# Sh_Coccinelle.net
KiCad netlist of a schematic drawn in Altium Designer
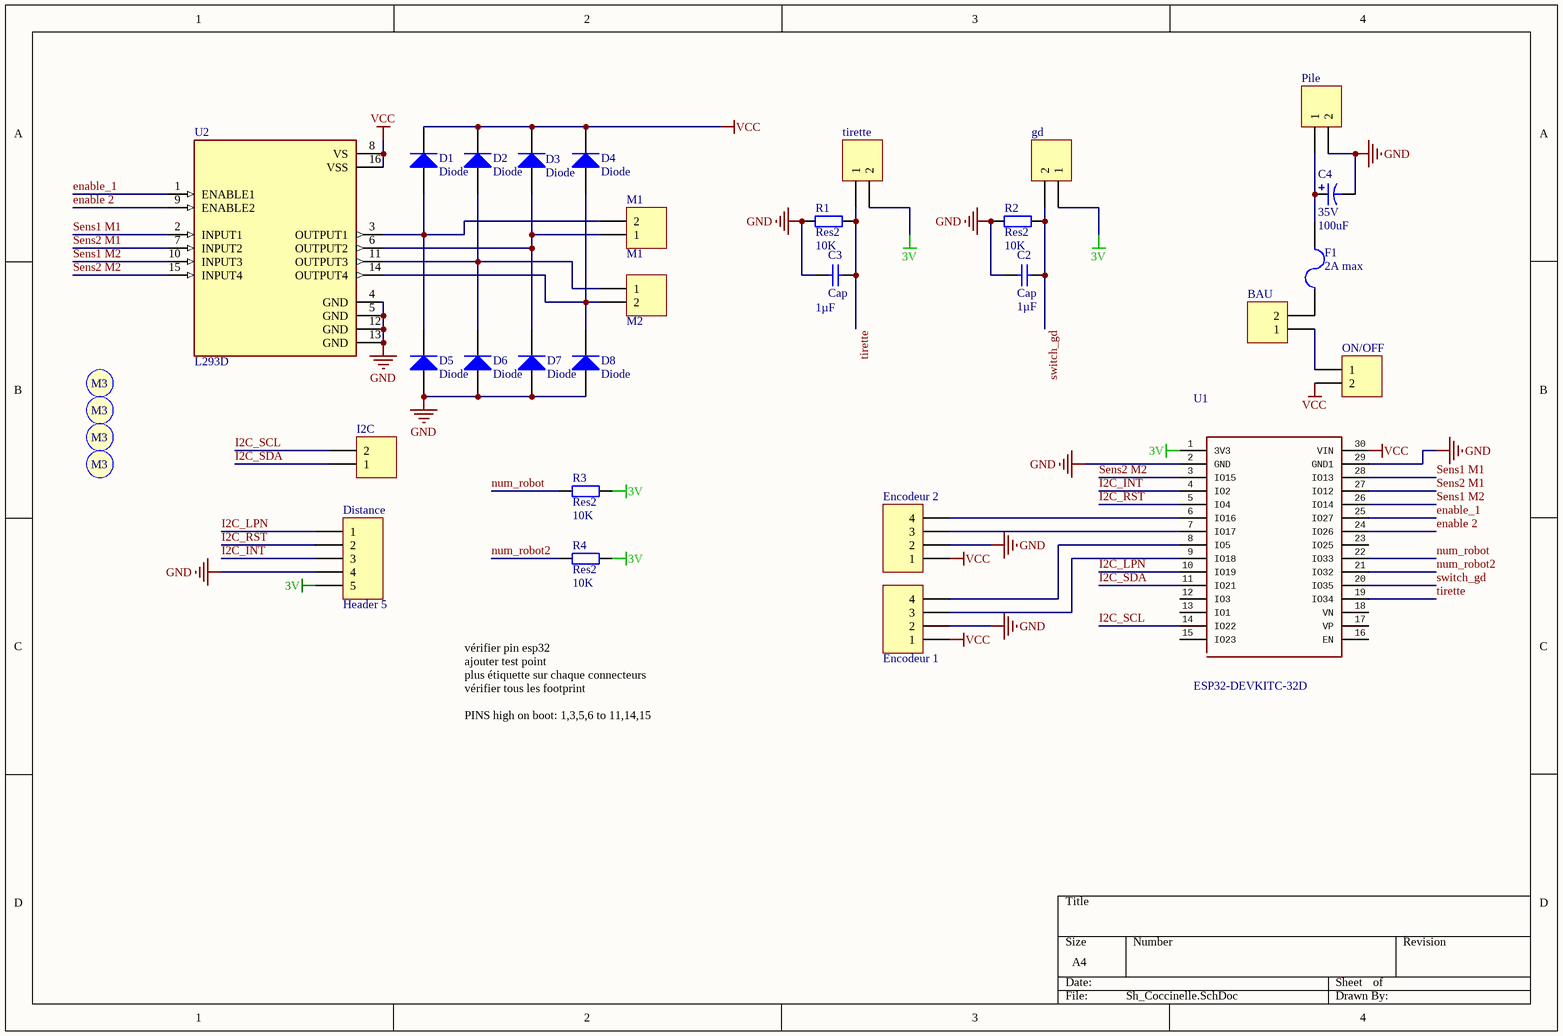
[diagram p0: Sh_Coccinelle.SchDoc]

(export (version "E")
  (design (tool "Eeschema 10.0.6"))
  (components
    (comp (ref "BAU")
      (value "~")
      (footprint "S2B-XH-A")
      (description "Header, 2-Pin, Right Angle")
      (fields (field (name "PUBLISHER") "Altium Limited"))
      (libsource (lib "Miscellaneous Connectors") (part "Header 2H"))
    )
    (comp (ref "C2")
      (value "Cap")
      (footprint "Capacitor 1206")
      (description "Capacitor")
      (fields (field (name "ALTIUM_VALUE") "1µF") (field (name "PUBLISHER") "Altium Limited"))
      (libsource (lib "Miscellaneous Devices") (part "Cap"))
    )
    (comp (ref "C3")
      (value "Cap")
      (footprint "Capacitor 1206")
      (description "Capacitor")
      (fields (field (name "ALTIUM_VALUE") "1µF") (field (name "PUBLISHER") "Altium Limited"))
      (libsource (lib "Miscellaneous Devices") (part "Cap"))
    )
    (comp (ref "C4")
      (value "35V")
      (footprint "Condensateur")
      (description "Polarized Capacitor (Radial)")
      (fields (field (name "ALTIUM_VALUE") "100uF") (field (name "PUBLISHER") "Altium Limited"))
      (libsource (lib "Miscellaneous Devices") (part "Cap Pol1"))
    )
    (comp (ref "D1")
      (value "Diode")
      (footprint "SMB")
      (description "Default Diode")
      (fields (field (name "PUBLISHER") "Altium Limited"))
      (libsource (lib "Miscellaneous Devices") (part "Diode"))
    )
    (comp (ref "D2")
      (value "Diode")
      (footprint "SMB")
      (description "Default Diode")
      (fields (field (name "PUBLISHER") "Altium Limited"))
      (libsource (lib "Miscellaneous Devices") (part "Diode"))
    )
    (comp (ref "D3")
      (value "Diode")
      (footprint "SMB")
      (description "Default Diode")
      (fields (field (name "PUBLISHER") "Altium Limited"))
      (libsource (lib "Miscellaneous Devices") (part "Diode"))
    )
    (comp (ref "D4")
      (value "Diode")
      (footprint "SMB")
      (description "Default Diode")
      (fields (field (name "PUBLISHER") "Altium Limited"))
      (libsource (lib "Miscellaneous Devices") (part "Diode"))
    )
    (comp (ref "D5")
      (value "Diode")
      (footprint "SMB")
      (description "Default Diode")
      (fields (field (name "PUBLISHER") "Altium Limited"))
      (libsource (lib "Miscellaneous Devices") (part "Diode"))
    )
    (comp (ref "D6")
      (value "Diode")
      (footprint "SMB")
      (description "Default Diode")
      (fields (field (name "PUBLISHER") "Altium Limited"))
      (libsource (lib "Miscellaneous Devices") (part "Diode"))
    )
    (comp (ref "D7")
      (value "Diode")
      (footprint "SMB")
      (description "Default Diode")
      (fields (field (name "PUBLISHER") "Altium Limited"))
      (libsource (lib "Miscellaneous Devices") (part "Diode"))
    )
    (comp (ref "D8")
      (value "Diode")
      (footprint "SMB")
      (description "Default Diode")
      (fields (field (name "PUBLISHER") "Altium Limited"))
      (libsource (lib "Miscellaneous Devices") (part "Diode"))
    )
    (comp (ref "Distance")
      (value "Header 5")
      (footprint "B5BXHAMLFSN")
      (description "Header, 5-Pin")
      (fields (field (name "PUBLISHER") "Altium Limited"))
      (libsource (lib "Miscellaneous Connectors") (part "Header 5"))
    )
    (comp (ref "Encodeur 1")
      (value "~")
      (footprint "B4BXHALFSN")
      (description "Header, 4-Pin, Right Angle")
      (fields (field (name "PUBLISHER") "Altium Limited"))
      (libsource (lib "Miscellaneous Connectors") (part "Header 4H"))
    )
    (comp (ref "Encodeur 2")
      (value "~")
      (footprint "B4BXHALFSN")
      (description "Header, 4-Pin, Right Angle")
      (fields (field (name "PUBLISHER") "Altium Limited"))
      (libsource (lib "Miscellaneous Connectors") (part "Header 4H"))
    )
    (comp (ref "F1")
      (value "2A max")
      (footprint "PIN-W2/E2.8")
      (description "Fuse")
      (fields (field (name "PUBLISHER") "Altium Limited"))
      (libsource (lib "Miscellaneous Devices") (part "Fuse 2"))
    )
    (comp (ref "gd")
      (value "~")
      (footprint "S2B-XH-A")
      (description "Header, 2-Pin, Right Angle")
      (fields (field (name "PUBLISHER") "Altium Limited"))
      (libsource (lib "") (part "Header 2H_1"))
    )
    (comp (ref "I2C")
      (value "~")
      (footprint "S2B-XH-A")
      (description "Header, 2-Pin, Right Angle")
      (fields (field (name "PUBLISHER") "Altium Limited"))
      (libsource (lib "") (part "Header 2H_2"))
    )
    (comp (ref "M1")
      (value "M1")
      (footprint "S2B-XH-A")
      (description "Header, 2-Pin, Right Angle")
      (fields (field (name "PUBLISHER") "Altium Limited"))
      (libsource (lib "") (part "Header 2H_2"))
    )
    (comp (ref "M2")
      (value "M2")
      (footprint "S2B-XH-A")
      (description "Header, 2-Pin, Right Angle")
      (fields (field (name "PUBLISHER") "Altium Limited"))
      (libsource (lib "") (part "Header 2H_1"))
    )
    (comp (ref "ON/OFF")
      (value "~")
      (footprint "S2B-XH-A")
      (description "Header, 2-Pin, Right Angle")
      (fields (field (name "PUBLISHER") "Altium Limited"))
      (libsource (lib "") (part "Header 2H_1"))
    )
    (comp (ref "Pile")
      (value "~")
      (footprint "S2B-XH-A")
      (description "Header, 2-Pin, Right Angle")
      (fields (field (name "PUBLISHER") "Altium Limited"))
      (libsource (lib "") (part "Header 2H_2"))
    )
    (comp (ref "R1")
      (value "Res2")
      (footprint "Resistor 1206")
      (description "Resistor")
      (fields (field (name "ALTIUM_VALUE") "10K") (field (name "PUBLISHER") "Altium Limited"))
      (libsource (lib "Miscellaneous Devices") (part "Res2"))
    )
    (comp (ref "R2")
      (value "Res2")
      (footprint "Resistor 1206")
      (description "Resistor")
      (fields (field (name "ALTIUM_VALUE") "10K") (field (name "PUBLISHER") "Altium Limited"))
      (libsource (lib "Miscellaneous Devices") (part "Res2"))
    )
    (comp (ref "R3")
      (value "Res2")
      (footprint "Resistor 1206")
      (description "Resistor")
      (fields (field (name "ALTIUM_VALUE") "10K") (field (name "PUBLISHER") "Altium Limited"))
      (libsource (lib "Miscellaneous Devices") (part "Res2"))
    )
    (comp (ref "R4")
      (value "Res2")
      (footprint "Resistor 1206")
      (description "Resistor")
      (fields (field (name "ALTIUM_VALUE") "10K") (field (name "PUBLISHER") "Altium Limited"))
      (libsource (lib "Miscellaneous Devices") (part "Res2"))
    )
    (comp (ref "S1")
      (value "Screw M3")
      (footprint "Screw M3")
      (libsource (lib "Robot_2020") (part "Screw M3"))
    )
    (comp (ref "S2")
      (value "Screw M3")
      (footprint "Screw M3")
      (libsource (lib "Robot_2020") (part "Screw M3"))
    )
    (comp (ref "S3")
      (value "Screw M3")
      (footprint "Screw M3")
      (libsource (lib "Robot_2020") (part "Screw M3"))
    )
    (comp (ref "S4")
      (value "Screw M3")
      (footprint "Screw M3")
      (libsource (lib "Robot_2020") (part "Screw M3"))
    )
    (comp (ref "tirette")
      (value "~")
      (footprint "S2B-XH-A")
      (description "Header, 2-Pin, Right Angle")
      (fields (field (name "PUBLISHER") "Altium Limited"))
      (libsource (lib "") (part "Header 2H_2"))
    )
    (comp (ref "U1")
      (value "ESP32-DEVKITC-32D")
      (footprint "MODULE_ESP32-DEVKITV1")
      (description "Eval Board For Esp-Wroom-32")
      (fields (field (name "MF") "Espressif Systems"))
      (libsource (lib "AltiumLibraryDDT") (part "ESP32-DEVKITC-32D"))
    )
    (comp (ref "U2")
      (value "L293D")
      (footprint "DIP880W50P254L2000H510Q16")
      (description "Bipolar Motor Driver - Parallel 16-PowerDIP")
      (fields (field (name "MF") "STMicroelectronics"))
      (libsource (lib "L293D") (part "L293D"))
    )
  )
  (nets
    (net (code "1") (name "/I2C_INT") (class "Default")
      (node (ref "Distance") (pin "3") (pinfunction "3_3") (pintype "passive"))
      (node (ref "U1") (pin "4") (pinfunction "IO2_4") (pintype "passive"))
    )
    (net (code "2") (name "/I2C_LPN") (class "Default")
      (node (ref "Distance") (pin "1") (pinfunction "1_1") (pintype "passive"))
      (node (ref "U1") (pin "10") (pinfunction "IO19_10") (pintype "passive"))
    )
    (net (code "3") (name "/I2C_RST") (class "Default")
      (node (ref "Distance") (pin "2") (pinfunction "2_2") (pintype "passive"))
      (node (ref "U1") (pin "5") (pinfunction "IO4_5") (pintype "passive"))
    )
    (net (code "4") (name "/I2C_SCL") (class "Default")
      (node (ref "I2C") (pin "2") (pinfunction "2_2") (pintype "passive"))
      (node (ref "U1") (pin "14") (pinfunction "IO22_14") (pintype "passive"))
    )
    (net (code "5") (name "/I2C_SDA") (class "Default")
      (node (ref "I2C") (pin "1") (pinfunction "1_1") (pintype "passive"))
      (node (ref "U1") (pin "11") (pinfunction "IO21_11") (pintype "passive"))
    )
    (net (code "6") (name "/Sens1 M1") (class "Default")
      (node (ref "U1") (pin "28") (pinfunction "IO13_28") (pintype "passive"))
      (node (ref "U2") (pin "2") (pinfunction "INPUT1_2") (pintype "input"))
    )
    (net (code "7") (name "/Sens1 M2") (class "Default")
      (node (ref "U1") (pin "26") (pinfunction "IO14_26") (pintype "passive"))
      (node (ref "U2") (pin "10") (pinfunction "INPUT3_10") (pintype "input"))
    )
    (net (code "8") (name "/Sens2 M1") (class "Default")
      (node (ref "U1") (pin "27") (pinfunction "IO12_27") (pintype "passive"))
      (node (ref "U2") (pin "7") (pinfunction "INPUT2_7") (pintype "input"))
    )
    (net (code "9") (name "/Sens2 M2") (class "Default")
      (node (ref "U1") (pin "3") (pinfunction "IO15_3") (pintype "passive"))
      (node (ref "U2") (pin "15") (pinfunction "INPUT4_15") (pintype "input"))
    )
    (net (code "10") (name "/enable 2") (class "Default")
      (node (ref "U1") (pin "24") (pinfunction "IO26_24") (pintype "passive"))
      (node (ref "U2") (pin "9") (pinfunction "ENABLE2_9") (pintype "input"))
    )
    (net (code "11") (name "/enable_1") (class "Default")
      (node (ref "U1") (pin "25") (pinfunction "IO27_25") (pintype "passive"))
      (node (ref "U2") (pin "1") (pinfunction "ENABLE1_1") (pintype "input"))
    )
    (net (code "12") (name "/num_robot") (class "Default")
      (node (ref "R3") (pin "1") (pinfunction "1_1") (pintype "passive"))
      (node (ref "U1") (pin "22") (pinfunction "IO33_22") (pintype "passive"))
    )
    (net (code "13") (name "/num_robot2") (class "Default")
      (node (ref "R4") (pin "1") (pinfunction "1_1") (pintype "passive"))
      (node (ref "U1") (pin "21") (pinfunction "IO32_21") (pintype "passive"))
    )
    (net (code "14") (name "/switch_gd") (class "Default")
      (node (ref "C2") (pin "2") (pinfunction "2_2") (pintype "passive"))
      (node (ref "R2") (pin "2") (pinfunction "2_2") (pintype "passive"))
      (node (ref "U1") (pin "20") (pinfunction "IO35_20") (pintype "passive"))
      (node (ref "gd") (pin "2") (pinfunction "2_2") (pintype "passive"))
    )
    (net (code "15") (name "/tirette") (class "Default")
      (node (ref "C3") (pin "2") (pinfunction "2_2") (pintype "passive"))
      (node (ref "R1") (pin "2") (pinfunction "2_2") (pintype "passive"))
      (node (ref "U1") (pin "19") (pinfunction "IO34_19") (pintype "passive"))
      (node (ref "tirette") (pin "1") (pinfunction "1_1") (pintype "passive"))
    )
    (net (code "16") (name "3V") (class "Default")
      (node (ref "Distance") (pin "5") (pinfunction "5_5") (pintype "passive"))
      (node (ref "R3") (pin "2") (pinfunction "2_2") (pintype "passive"))
      (node (ref "R4") (pin "2") (pinfunction "2_2") (pintype "passive"))
      (node (ref "U1") (pin "1") (pinfunction "3V3_1") (pintype "passive"))
      (node (ref "gd") (pin "1") (pinfunction "1_1") (pintype "passive"))
      (node (ref "tirette") (pin "2") (pinfunction "2_2") (pintype "passive"))
    )
    (net (code "17") (name "GND") (class "Default")
      (node (ref "C2") (pin "1") (pinfunction "1_1") (pintype "passive"))
      (node (ref "C3") (pin "1") (pinfunction "1_1") (pintype "passive"))
      (node (ref "C4") (pin "2") (pinfunction "2_2") (pintype "passive"))
      (node (ref "D5") (pin "1") (pinfunction "A_1") (pintype "passive"))
      (node (ref "D6") (pin "1") (pinfunction "A_1") (pintype "passive"))
      (node (ref "D7") (pin "1") (pinfunction "A_1") (pintype "passive"))
      (node (ref "D8") (pin "1") (pinfunction "A_1") (pintype "passive"))
      (node (ref "Distance") (pin "4") (pinfunction "4_4") (pintype "passive"))
      (node (ref "Encodeur 1") (pin "2") (pinfunction "2_2") (pintype "passive"))
      (node (ref "Encodeur 2") (pin "2") (pinfunction "2_2") (pintype "passive"))
      (node (ref "Pile") (pin "2") (pinfunction "2_2") (pintype "passive"))
      (node (ref "R1") (pin "1") (pinfunction "1_1") (pintype "passive"))
      (node (ref "R2") (pin "1") (pinfunction "1_1") (pintype "passive"))
      (node (ref "U1") (pin "2") (pinfunction "GND_2") (pintype "passive"))
      (node (ref "U1") (pin "29") (pinfunction "GND1_29") (pintype "passive"))
      (node (ref "U2") (pin "12") (pinfunction "GND_12") (pintype "power_in"))
      (node (ref "U2") (pin "13") (pinfunction "GND_13") (pintype "power_in"))
      (node (ref "U2") (pin "4") (pinfunction "GND_4") (pintype "power_in"))
      (node (ref "U2") (pin "5") (pinfunction "GND_5") (pintype "power_in"))
    )
    (net (code "18") (name "Net-(BAU-Pad1)") (class "Default")
      (node (ref "BAU") (pin "1") (pinfunction "1_1") (pintype "passive"))
      (node (ref "ON/OFF") (pin "1") (pinfunction "1_1") (pintype "passive"))
    )
    (net (code "19") (name "Net-(BAU-Pad2)") (class "Default")
      (node (ref "BAU") (pin "2") (pinfunction "2_2") (pintype "passive"))
      (node (ref "F1") (pin "1") (pinfunction "1_1") (pintype "passive"))
    )
    (net (code "20") (name "Net-(C4-Pad1)") (class "Default")
      (node (ref "C4") (pin "1") (pinfunction "1_1") (pintype "passive"))
      (node (ref "F1") (pin "2") (pinfunction "2_2") (pintype "passive"))
      (node (ref "Pile") (pin "1") (pinfunction "1_1") (pintype "passive"))
    )
    (net (code "21") (name "Net-(D1-A)") (class "Default")
      (node (ref "D1") (pin "1") (pinfunction "A_1") (pintype "passive"))
      (node (ref "D5") (pin "2") (pinfunction "K_2") (pintype "passive"))
      (node (ref "M1") (pin "2") (pinfunction "2_2") (pintype "passive"))
      (node (ref "U2") (pin "3") (pinfunction "OUTPUT1_3") (pintype "output"))
    )
    (net (code "22") (name "Net-(D2-A)") (class "Default")
      (node (ref "D2") (pin "1") (pinfunction "A_1") (pintype "passive"))
      (node (ref "D6") (pin "2") (pinfunction "K_2") (pintype "passive"))
      (node (ref "M2") (pin "1") (pinfunction "1_1") (pintype "passive"))
      (node (ref "U2") (pin "11") (pinfunction "OUTPUT3_11") (pintype "output"))
    )
    (net (code "23") (name "Net-(D3-A)") (class "Default")
      (node (ref "D3") (pin "1") (pinfunction "A_1") (pintype "passive"))
      (node (ref "D7") (pin "2") (pinfunction "K_2") (pintype "passive"))
      (node (ref "M1") (pin "1") (pinfunction "1_1") (pintype "passive"))
      (node (ref "U2") (pin "6") (pinfunction "OUTPUT2_6") (pintype "output"))
    )
    (net (code "24") (name "Net-(D4-A)") (class "Default")
      (node (ref "D4") (pin "1") (pinfunction "A_1") (pintype "passive"))
      (node (ref "D8") (pin "2") (pinfunction "K_2") (pintype "passive"))
      (node (ref "M2") (pin "2") (pinfunction "2_2") (pintype "passive"))
      (node (ref "U2") (pin "14") (pinfunction "OUTPUT4_14") (pintype "output"))
    )
    (net (code "25") (name "Net-(U1-IO5)") (class "Default")
      (node (ref "Encodeur 1") (pin "4") (pinfunction "4_4") (pintype "passive"))
      (node (ref "U1") (pin "8") (pinfunction "IO5_8") (pintype "passive"))
    )
    (net (code "26") (name "Net-(U1-IO16)") (class "Default")
      (node (ref "Encodeur 2") (pin "4") (pinfunction "4_4") (pintype "passive"))
      (node (ref "U1") (pin "6") (pinfunction "IO16_6") (pintype "passive"))
    )
    (net (code "27") (name "Net-(U1-IO17)") (class "Default")
      (node (ref "Encodeur 2") (pin "3") (pinfunction "3_3") (pintype "passive"))
      (node (ref "U1") (pin "7") (pinfunction "IO17_7") (pintype "passive"))
    )
    (net (code "28") (name "Net-(U1-IO18)") (class "Default")
      (node (ref "Encodeur 1") (pin "3") (pinfunction "3_3") (pintype "passive"))
      (node (ref "U1") (pin "9") (pinfunction "IO18_9") (pintype "passive"))
    )
    (net (code "29") (name "VCC") (class "Default")
      (node (ref "D1") (pin "2") (pinfunction "K_2") (pintype "passive"))
      (node (ref "D2") (pin "2") (pinfunction "K_2") (pintype "passive"))
      (node (ref "D3") (pin "2") (pinfunction "K_2") (pintype "passive"))
      (node (ref "D4") (pin "2") (pinfunction "K_2") (pintype "passive"))
      (node (ref "Encodeur 1") (pin "1") (pinfunction "1_1") (pintype "passive"))
      (node (ref "Encodeur 2") (pin "1") (pinfunction "1_1") (pintype "passive"))
      (node (ref "ON/OFF") (pin "2") (pinfunction "2_2") (pintype "passive"))
      (node (ref "U1") (pin "30") (pinfunction "VIN_30") (pintype "passive"))
      (node (ref "U2") (pin "16") (pinfunction "VSS_16") (pintype "power_in"))
      (node (ref "U2") (pin "8") (pinfunction "VS_8") (pintype "power_in"))
    )
    (net (code "30") (name "unconnected-(U1-EN-Pad16)") (class "Default")
      (node (ref "U1") (pin "16") (pinfunction "EN_16") (pintype "passive"))
    )
    (net (code "31") (name "unconnected-(U1-IO1-Pad13)") (class "Default")
      (node (ref "U1") (pin "13") (pinfunction "IO1_13") (pintype "passive"))
    )
    (net (code "32") (name "unconnected-(U1-IO3-Pad12)") (class "Default")
      (node (ref "U1") (pin "12") (pinfunction "IO3_12") (pintype "passive"))
    )
    (net (code "33") (name "unconnected-(U1-IO23-Pad15)") (class "Default")
      (node (ref "U1") (pin "15") (pinfunction "IO23_15") (pintype "passive"))
    )
    (net (code "34") (name "unconnected-(U1-IO25-Pad23)") (class "Default")
      (node (ref "U1") (pin "23") (pinfunction "IO25_23") (pintype "passive"))
    )
    (net (code "35") (name "unconnected-(U1-VN-Pad18)") (class "Default")
      (node (ref "U1") (pin "18") (pinfunction "VN_18") (pintype "passive"))
    )
    (net (code "36") (name "unconnected-(U1-VP-Pad17)") (class "Default")
      (node (ref "U1") (pin "17") (pinfunction "VP_17") (pintype "passive"))
    )
  )
)
